# Schematic.net
KiCad netlist of a schematic drawn in Altium Designer
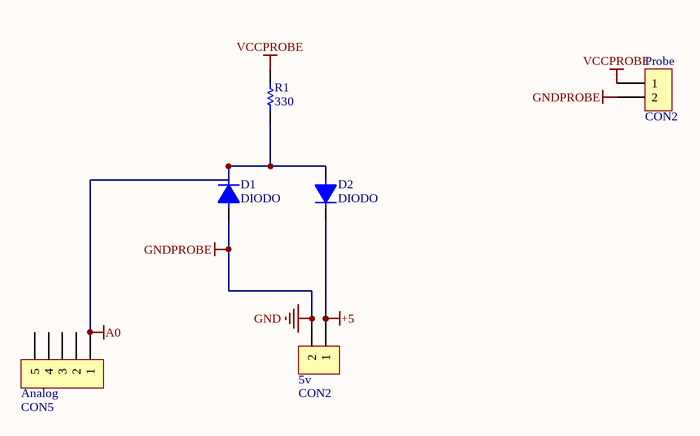
[diagram p0: Schematic.SchDoc]

(export (version "E")
  (design (tool "Eeschema 10.0.6"))
  (components
    (comp (ref "5v") (value "CON2") (footprint "SIP2") (libsource (lib "LIBEBAL") (part "CON2")))
    (comp (ref "Analog") (value "CON5") (footprint "SIP5") (libsource (lib "LIBEBAL") (part "CON5")))
    (comp (ref "D1") (value "DIODO") (footprint "DO41") (libsource (lib "LIBEBAL") (part "DIODO")))
    (comp (ref "D2") (value "DIODO") (footprint "DO41") (libsource (lib "LIBEBAL") (part "DIODO")))
    (comp (ref "Probe") (value "CON2") (footprint "SIP2") (libsource (lib "") (part "CON2_1")))
    (comp (ref "R1") (value "330") (footprint "RES400") (libsource (lib "LIBEBAL") (part "RES")))
  )
  (nets
    (net (code "1") (name "+5") (class "Default")
      (node (ref "5v") (pin "1") (pinfunction "1_1") (pintype "passive"))
      (node (ref "D2") (pin "2") (pinfunction "2_2") (pintype "passive"))
    )
    (net (code "2") (name "A0") (class "Default")
      (node (ref "Analog") (pin "1") (pinfunction "1_1") (pintype "passive"))
      (node (ref "D1") (pin "2") (pinfunction "2_2") (pintype "passive"))
      (node (ref "D2") (pin "1") (pinfunction "1_1") (pintype "passive"))
      (node (ref "R1") (pin "1") (pinfunction "1_1") (pintype "passive"))
    )
    (net (code "3") (name "GND") (class "Default")
      (node (ref "5v") (pin "2") (pinfunction "2_2") (pintype "passive"))
      (node (ref "D1") (pin "1") (pinfunction "1_1") (pintype "passive"))
      (node (ref "Probe") (pin "2") (pinfunction "2_2") (pintype "passive"))
    )
    (net (code "4") (name "VCCPROBE") (class "Default")
      (node (ref "Probe") (pin "1") (pinfunction "1_1") (pintype "passive"))
      (node (ref "R1") (pin "2") (pinfunction "2_2") (pintype "passive"))
    )
    (net (code "5") (name "unconnected-(Analog-Pad2)") (class "Default")
      (node (ref "Analog") (pin "2") (pinfunction "2_2") (pintype "passive"))
    )
    (net (code "6") (name "unconnected-(Analog-Pad3)") (class "Default")
      (node (ref "Analog") (pin "3") (pinfunction "3_3") (pintype "passive"))
    )
    (net (code "7") (name "unconnected-(Analog-Pad4)") (class "Default")
      (node (ref "Analog") (pin "4") (pinfunction "4_4") (pintype "passive"))
    )
    (net (code "8") (name "unconnected-(Analog-Pad5)") (class "Default")
      (node (ref "Analog") (pin "5") (pinfunction "5_5") (pintype "passive"))
    )
  )
)
